# fotoresistenza_v1_rev0.net
KiCad netlist of a schematic drawn in EAGLE
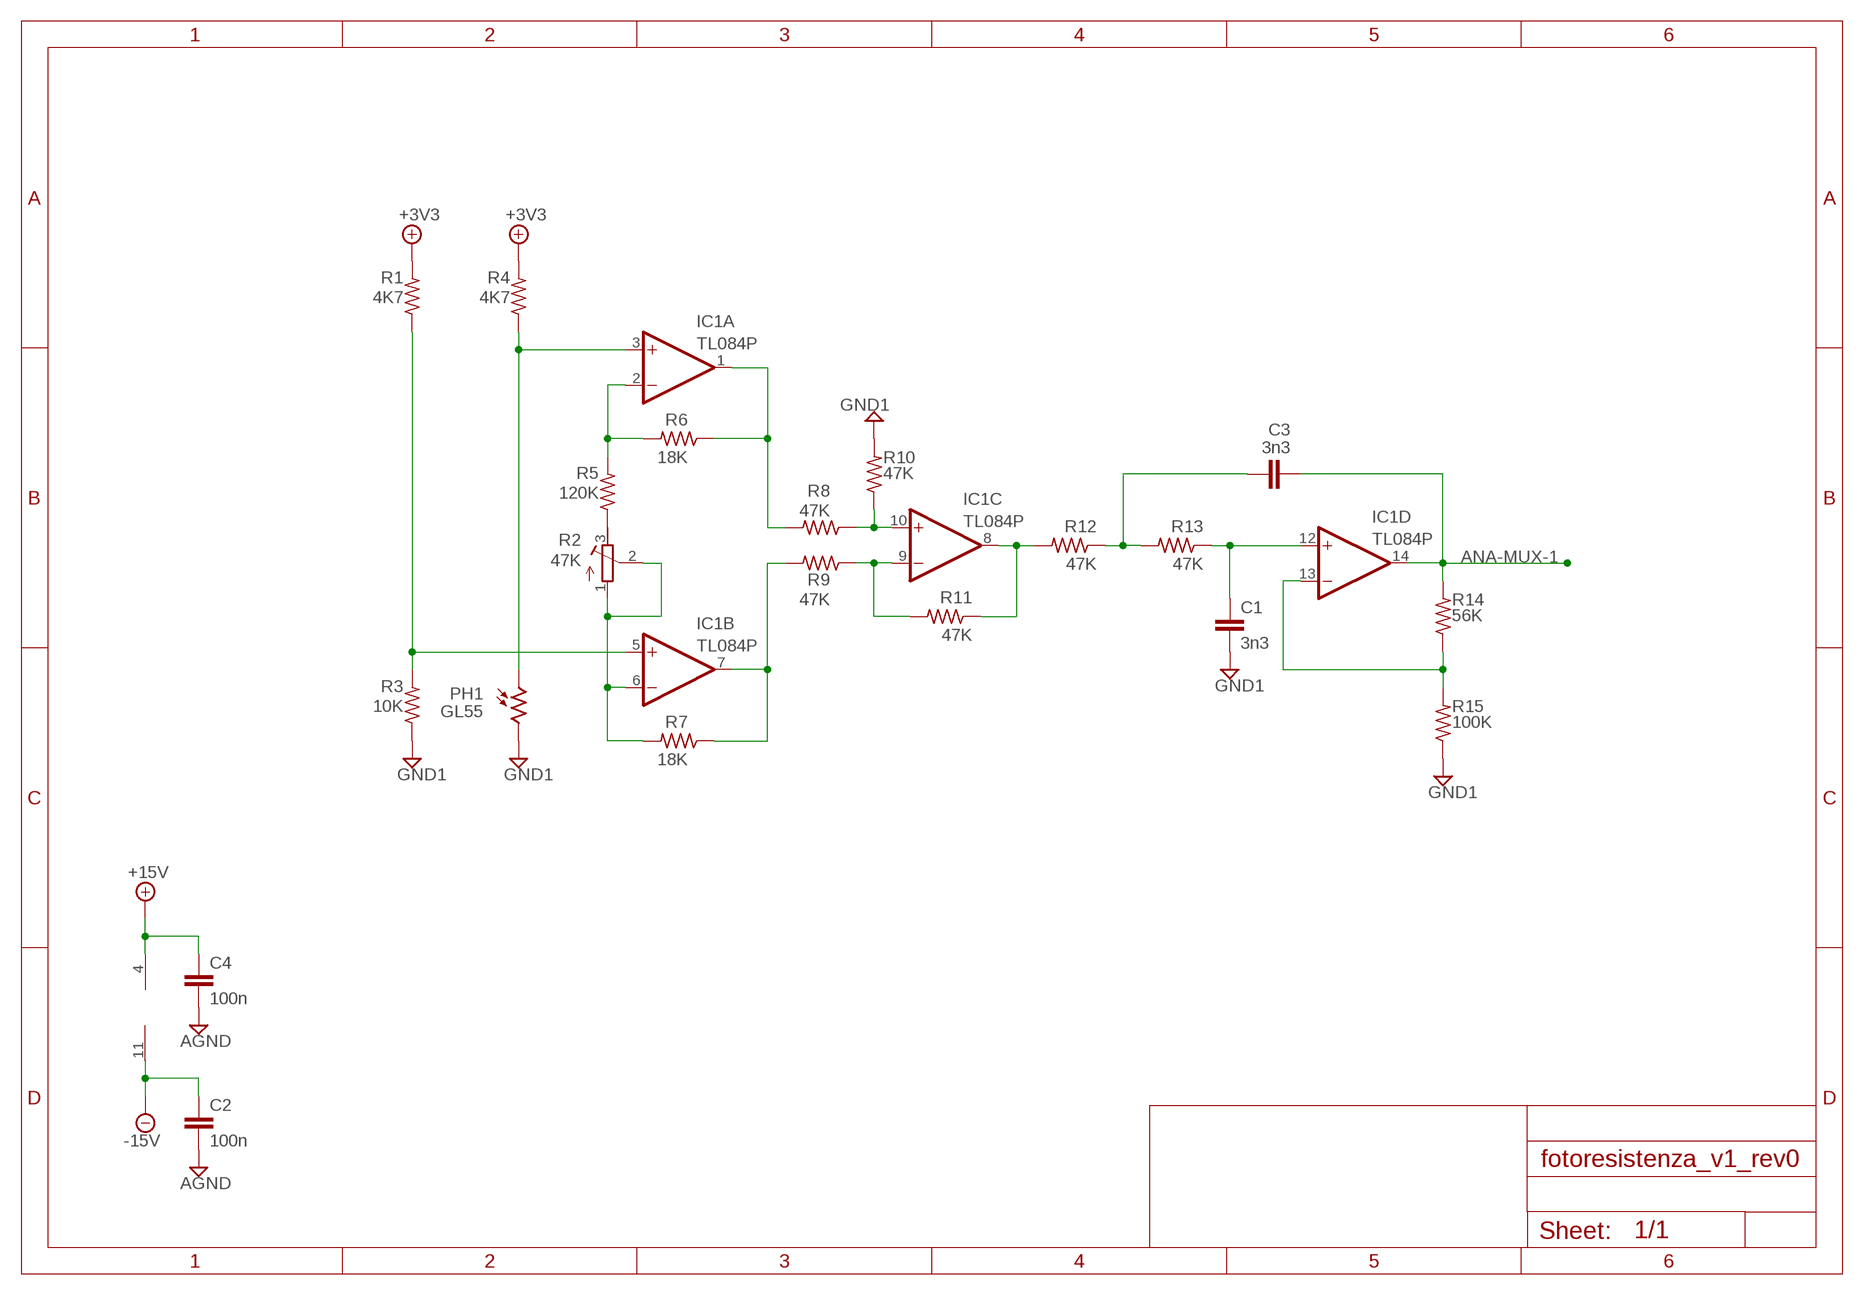
[diagram p0: schematic, sheet 1]

(export (version "E")
  (design (tool "Eeschema 10.0.6"))
  (components
    (comp (ref "C1")
      (value "3n3")
      (footprint "eagle-import:C025-025X050")
      (libsource (lib "eagle-import") (part "C-EU025-025X050"))
    )
    (comp (ref "C2")
      (value "100n")
      (footprint "eagle-import:C025-025X050")
      (libsource (lib "eagle-import") (part "C-EU025-025X050"))
    )
    (comp (ref "C3")
      (value "3n3")
      (footprint "eagle-import:C025-025X050")
      (libsource (lib "eagle-import") (part "C-EU025-025X050"))
    )
    (comp (ref "C4")
      (value "100n")
      (footprint "eagle-import:C025-025X050")
      (libsource (lib "eagle-import") (part "C-EU025-025X050"))
    )
    (comp (ref "IC1")
      (value "TL084P")
      (footprint "eagle-import:DIL14")
      (libsource (lib "eagle-import") (part "TL084P"))
    )
    (comp (ref "PH1")
      (value "GL55")
      (footprint "eagle-import:TO-8_B10")
      (fields (field (name "TYPE") "GL55"))
      (libsource (lib "eagle-import") (part "?1060B_23"))
    )
    (comp (ref "R1")
      (value "4K7")
      (footprint "eagle-import:0204_7")
      (libsource (lib "eagle-import") (part "R-US_0204/7"))
    )
    (comp (ref "R2")
      (value "47K")
      (footprint "eagle-import:RTRIM64W")
      (libsource (lib "eagle-import") (part "R-TRIMM64W"))
    )
    (comp (ref "R3")
      (value "10K")
      (footprint "eagle-import:0204_7")
      (libsource (lib "eagle-import") (part "R-US_0204/7"))
    )
    (comp (ref "R4")
      (value "4K7")
      (footprint "eagle-import:0204_7")
      (libsource (lib "eagle-import") (part "R-US_0204/7"))
    )
    (comp (ref "R5")
      (value "120K")
      (footprint "eagle-import:0204_7")
      (libsource (lib "eagle-import") (part "R-US_0204/7"))
    )
    (comp (ref "R6")
      (value "18K")
      (footprint "eagle-import:0204_7")
      (libsource (lib "eagle-import") (part "R-US_0204/7"))
    )
    (comp (ref "R7")
      (value "18K")
      (footprint "eagle-import:0204_7")
      (libsource (lib "eagle-import") (part "R-US_0204/7"))
    )
    (comp (ref "R8")
      (value "47K")
      (footprint "eagle-import:0204_7")
      (libsource (lib "eagle-import") (part "R-US_0204/7"))
    )
    (comp (ref "R9")
      (value "47K")
      (footprint "eagle-import:0204_7")
      (libsource (lib "eagle-import") (part "R-US_0204/7"))
    )
    (comp (ref "R10")
      (value "47K")
      (footprint "eagle-import:0204_7")
      (libsource (lib "eagle-import") (part "R-US_0204/7"))
    )
    (comp (ref "R11")
      (value "47K")
      (footprint "eagle-import:0204_7")
      (libsource (lib "eagle-import") (part "R-US_0204/7"))
    )
    (comp (ref "R12")
      (value "47K")
      (footprint "eagle-import:0204_7")
      (libsource (lib "eagle-import") (part "R-US_0204/7"))
    )
    (comp (ref "R13")
      (value "47K")
      (footprint "eagle-import:0204_7")
      (libsource (lib "eagle-import") (part "R-US_0204/7"))
    )
    (comp (ref "R14")
      (value "56K")
      (footprint "eagle-import:0204_7")
      (libsource (lib "eagle-import") (part "R-US_0204/7"))
    )
    (comp (ref "R15")
      (value "100K")
      (footprint "eagle-import:0204_7")
      (libsource (lib "eagle-import") (part "R-US_0204/7"))
    )
  )
  (nets
    (net (code "1") (name "+3V3") (class "Default")
      (node (ref "R1") (pin "2") (pinfunction "2_2") (pintype "passive"))
      (node (ref "R4") (pin "2") (pinfunction "2_2") (pintype "passive"))
    )
    (net (code "2") (name "+15V") (class "Default")
      (node (ref "C4") (pin "1") (pinfunction "1_1") (pintype "passive"))
      (node (ref "IC1") (pin "4") (pinfunction "V+_4") (pintype "power_in"))
    )
    (net (code "3") (name "-15V") (class "Default")
      (node (ref "C2") (pin "1") (pinfunction "1_1") (pintype "passive"))
      (node (ref "IC1") (pin "11") (pinfunction "V-_11") (pintype "power_in"))
    )
    (net (code "4") (name "/ANA-MUX-1") (class "Default")
      (node (ref "C3") (pin "2") (pinfunction "2_2") (pintype "passive"))
      (node (ref "IC1") (pin "14") (pinfunction "OUT_14") (pintype "output"))
      (node (ref "R14") (pin "2") (pinfunction "2_2") (pintype "passive"))
    )
    (net (code "5") (name "AGND") (class "Default")
      (node (ref "C2") (pin "2") (pinfunction "2_2") (pintype "passive"))
      (node (ref "C4") (pin "2") (pinfunction "2_2") (pintype "passive"))
    )
    (net (code "6") (name "GND1") (class "Default")
      (node (ref "C1") (pin "2") (pinfunction "2_2") (pintype "passive"))
      (node (ref "PH1") (pin "2") (pinfunction "2_2") (pintype "passive"))
      (node (ref "R10") (pin "2") (pinfunction "2_2") (pintype "passive"))
      (node (ref "R15") (pin "1") (pinfunction "1_1") (pintype "passive"))
      (node (ref "R3") (pin "1") (pinfunction "1_1") (pintype "passive"))
    )
    (net (code "7") (name "Net-(C3-Pad1)") (class "Default")
      (node (ref "C3") (pin "1") (pinfunction "1_1") (pintype "passive"))
      (node (ref "R12") (pin "1") (pinfunction "1_1") (pintype "passive"))
      (node (ref "R13") (pin "2") (pinfunction "2_2") (pintype "passive"))
    )
    (net (code "8") (name "Net-(IC1A-+IN)") (class "Default")
      (node (ref "IC1") (pin "3") (pinfunction "+IN_3") (pintype "input"))
      (node (ref "PH1") (pin "1") (pinfunction "1_1") (pintype "passive"))
      (node (ref "R4") (pin "1") (pinfunction "1_1") (pintype "passive"))
    )
    (net (code "9") (name "Net-(IC1A--IN)") (class "Default")
      (node (ref "IC1") (pin "2") (pinfunction "-IN_2") (pintype "input"))
      (node (ref "R5") (pin "2") (pinfunction "2_2") (pintype "passive"))
      (node (ref "R6") (pin "2") (pinfunction "2_2") (pintype "passive"))
    )
    (net (code "10") (name "Net-(IC1A-OUT)") (class "Default")
      (node (ref "IC1") (pin "1") (pinfunction "OUT_1") (pintype "output"))
      (node (ref "R6") (pin "1") (pinfunction "1_1") (pintype "passive"))
      (node (ref "R8") (pin "2") (pinfunction "2_2") (pintype "passive"))
    )
    (net (code "11") (name "Net-(IC1B-+IN)") (class "Default")
      (node (ref "IC1") (pin "5") (pinfunction "+IN_5") (pintype "input"))
      (node (ref "R1") (pin "1") (pinfunction "1_1") (pintype "passive"))
      (node (ref "R3") (pin "2") (pinfunction "2_2") (pintype "passive"))
    )
    (net (code "12") (name "Net-(IC1B--IN)") (class "Default")
      (node (ref "IC1") (pin "6") (pinfunction "-IN_6") (pintype "input"))
      (node (ref "R2") (pin "1") (pinfunction "E_1") (pintype "passive"))
      (node (ref "R2") (pin "2") (pinfunction "S_2") (pintype "passive"))
      (node (ref "R7") (pin "2") (pinfunction "2_2") (pintype "passive"))
    )
    (net (code "13") (name "Net-(IC1B-OUT)") (class "Default")
      (node (ref "IC1") (pin "7") (pinfunction "OUT_7") (pintype "output"))
      (node (ref "R7") (pin "1") (pinfunction "1_1") (pintype "passive"))
      (node (ref "R9") (pin "2") (pinfunction "2_2") (pintype "passive"))
    )
    (net (code "14") (name "Net-(IC1C-+IN)") (class "Default")
      (node (ref "IC1") (pin "10") (pinfunction "+IN_10") (pintype "input"))
      (node (ref "R10") (pin "1") (pinfunction "1_1") (pintype "passive"))
      (node (ref "R8") (pin "1") (pinfunction "1_1") (pintype "passive"))
    )
    (net (code "15") (name "Net-(IC1C--IN)") (class "Default")
      (node (ref "IC1") (pin "9") (pinfunction "-IN_9") (pintype "input"))
      (node (ref "R11") (pin "2") (pinfunction "2_2") (pintype "passive"))
      (node (ref "R9") (pin "1") (pinfunction "1_1") (pintype "passive"))
    )
    (net (code "16") (name "Net-(IC1C-OUT)") (class "Default")
      (node (ref "IC1") (pin "8") (pinfunction "OUT_8") (pintype "output"))
      (node (ref "R11") (pin "1") (pinfunction "1_1") (pintype "passive"))
      (node (ref "R12") (pin "2") (pinfunction "2_2") (pintype "passive"))
    )
    (net (code "17") (name "Net-(IC1D-+IN)") (class "Default")
      (node (ref "C1") (pin "1") (pinfunction "1_1") (pintype "passive"))
      (node (ref "IC1") (pin "12") (pinfunction "+IN_12") (pintype "input"))
      (node (ref "R13") (pin "1") (pinfunction "1_1") (pintype "passive"))
    )
    (net (code "18") (name "Net-(IC1D--IN)") (class "Default")
      (node (ref "IC1") (pin "13") (pinfunction "-IN_13") (pintype "input"))
      (node (ref "R14") (pin "1") (pinfunction "1_1") (pintype "passive"))
      (node (ref "R15") (pin "2") (pinfunction "2_2") (pintype "passive"))
    )
    (net (code "19") (name "Net-(R2-A)") (class "Default")
      (node (ref "R2") (pin "3") (pinfunction "A_3") (pintype "passive"))
      (node (ref "R5") (pin "1") (pinfunction "1_1") (pintype "passive"))
    )
  )
)
